# 03_MCU.net
KiCad netlist of a schematic drawn in Altium Designer
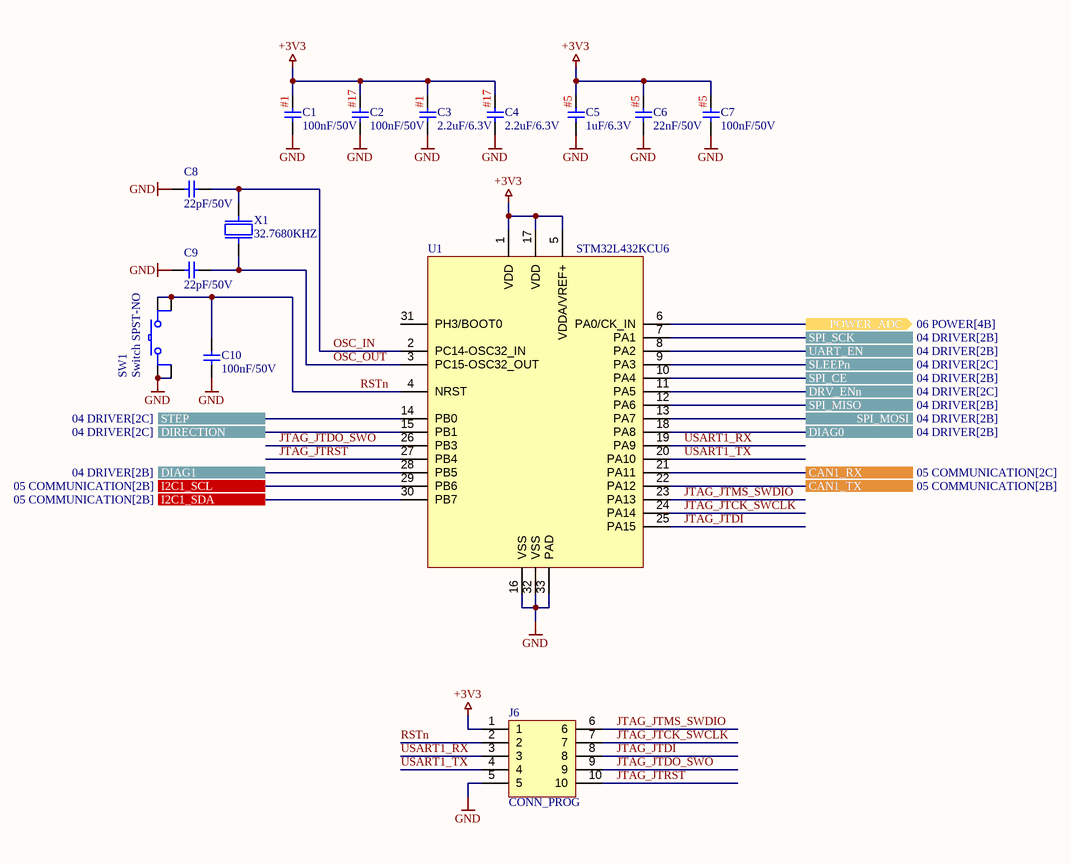
[diagram p0: 03 MCU.SchDoc]

(export (version "E")
  (design (tool "Eeschema 10.0.6"))
  (components
    (comp (ref "C1")
      (value "100nF/50V")
      (footprint "CAPC1005X06M-0402")
      (description "0.1 µF ±10% 50V Ceramic Capacitor X7R 0402 (1005 Metric)")
      (fields (field (name "MPN") "GRM155R71H104KE14D"))
      (libsource (lib "Symbol") (part "GRM155R71H104KE14D"))
    )
    (comp (ref "C2")
      (value "100nF/50V")
      (footprint "CAPC1005X06M-0402")
      (description "0.1 µF ±10% 50V Ceramic Capacitor X7R 0402 (1005 Metric)")
      (fields (field (name "MPN") "GRM155R71H104KE14D"))
      (libsource (lib "Symbol") (part "GRM155R71H104KE14D"))
    )
    (comp (ref "C3")
      (value "2.2uF/6.3V")
      (footprint "CAPC1005X06M-0402")
      (description "2.2 µF ±10% 6.3V Ceramic Capacitor X6S 0402 (1005 Metric)")
      (fields (field (name "MPN") "GRM155C80J225KE95D"))
      (libsource (lib "Symbol") (part "GRM155C80J225KE95D"))
    )
    (comp (ref "C4")
      (value "2.2uF/6.3V")
      (footprint "CAPC1005X06M-0402")
      (description "2.2 µF ±10% 6.3V Ceramic Capacitor X6S 0402 (1005 Metric)")
      (fields (field (name "MPN") "GRM155C80J225KE95D"))
      (libsource (lib "Symbol") (part "GRM155C80J225KE95D"))
    )
    (comp (ref "C5")
      (value "1uF/6.3V")
      (footprint "CAPC1005X06M-0402")
      (description "1 µF ±10% 6.3V Ceramic Capacitor X7R 0402 (1005 Metric)")
      (fields (field (name "MPN") "GRM155R70J105KA12J"))
      (libsource (lib "Symbol") (part "GRM155R70J105KA12J"))
    )
    (comp (ref "C6")
      (value "22nF/50V")
      (footprint "CAPC1005X06M-0402")
      (description "0.022 µF ±10% 50V Ceramic Capacitor X7R 0402 (1005 Metric)")
      (fields (field (name "MPN") "GRM155R71H223KA12D"))
      (libsource (lib "Symbol") (part "GRM155R71H223KA12D"))
    )
    (comp (ref "C7")
      (value "100nF/50V")
      (footprint "CAPC1005X06M-0402")
      (description "0.1 µF ±10% 50V Ceramic Capacitor X7R 0402 (1005 Metric)")
      (fields (field (name "MPN") "GRM155R71H104KE14D"))
      (libsource (lib "Symbol") (part "GRM155R71H104KE14D"))
    )
    (comp (ref "C8")
      (value "22pF/50V")
      (footprint "CAPC1005X06M-0402")
      (description "22 pF ±5% 50V Ceramic Capacitor C0G, NP0 0402 (1005 Metric)")
      (fields (field (name "MPN") "GRM1555C1H220JA01D"))
      (libsource (lib "Symbol") (part "GRM1555C1H220JA01D"))
    )
    (comp (ref "C9")
      (value "22pF/50V")
      (footprint "CAPC1005X06M-0402")
      (description "22 pF ±5% 50V Ceramic Capacitor C0G, NP0 0402 (1005 Metric)")
      (fields (field (name "MPN") "GRM1555C1H220JA01D"))
      (libsource (lib "Symbol") (part "GRM1555C1H220JA01D"))
    )
    (comp (ref "C10")
      (value "100nF/50V")
      (footprint "CAPC1005X06M-0402")
      (description "0.1 µF ±10% 50V Ceramic Capacitor X7R 0402 (1005 Metric)")
      (fields (field (name "MPN") "GRM155R71H104KE14D"))
      (libsource (lib "Symbol") (part "GRM155R71H104KE14D"))
    )
    (comp (ref "J6")
      (value "CONN_PROG")
      (footprint "CONN_PROG")
      (libsource (lib "Symbol") (part "CONN_PROG"))
    )
    (comp (ref "SW1")
      (value "Switch SPST-NO")
      (footprint "PTS815 SJM 250 SMTR LFS")
      (description "Tactile Switch SPST-NO Top Actuated Surface Mount")
      (fields (field (name "MPN") "PTS815 SJM 250 SMTR LFS"))
      (libsource (lib "Symbol") (part "PTS815 SJM 250 SMTR LFS"))
    )
    (comp (ref "U1")
      (value "STM32L432KCU6")
      (footprint "PQFN50P500X500X60_HS-33N")
      (libsource (lib "Symbol") (part "STM32L432KCU6"))
    )
    (comp (ref "X1")
      (value "32.7680KHZ")
      (footprint "2-SMD")
      (description "32.768 kHz ±20ppm Crystal 12.5pF 90 kOhms 2-SMD, No Lead")
      (fields (field (name "MPN") "ECS-.327-12.5-16-TR"))
      (libsource (lib "Symbol") (part "ECS-.327-12.5-16-TR"))
    )
  )
  (nets
    (net (code "1") (name "+3V3") (class "Default")
      (node (ref "C1") (pin "2") (pinfunction "2_2") (pintype "passive"))
      (node (ref "C2") (pin "2") (pinfunction "2_2") (pintype "passive"))
      (node (ref "C3") (pin "2") (pinfunction "2_2") (pintype "passive"))
      (node (ref "C4") (pin "2") (pinfunction "2_2") (pintype "passive"))
      (node (ref "C5") (pin "2") (pinfunction "2_2") (pintype "passive"))
      (node (ref "C6") (pin "2") (pinfunction "2_2") (pintype "passive"))
      (node (ref "C7") (pin "2") (pinfunction "2_2") (pintype "passive"))
      (node (ref "J6") (pin "1") (pinfunction "1_1") (pintype "passive"))
      (node (ref "U1") (pin "1") (pinfunction "VDD_1") (pintype "passive"))
      (node (ref "U1") (pin "17") (pinfunction "VDD_17") (pintype "passive"))
      (node (ref "U1") (pin "5") (pinfunction "VDDA/VREF+_5") (pintype "passive"))
    )
    (net (code "2") (name "/CAN1_RX") (class "Default")
      (node (ref "U1") (pin "21") (pinfunction "PA11_21") (pintype "passive"))
    )
    (net (code "3") (name "/CAN1_TX") (class "Default")
      (node (ref "U1") (pin "22") (pinfunction "PA12_22") (pintype "passive"))
    )
    (net (code "4") (name "/DIAG0") (class "Default")
      (node (ref "U1") (pin "18") (pinfunction "PA8_18") (pintype "passive"))
    )
    (net (code "5") (name "/DIAG1") (class "Default")
      (node (ref "U1") (pin "28") (pinfunction "PB5_28") (pintype "passive"))
    )
    (net (code "6") (name "/DIRECTION") (class "Default")
      (node (ref "U1") (pin "15") (pinfunction "PB1_15") (pintype "passive"))
    )
    (net (code "7") (name "/DRV_ENn") (class "Default")
      (node (ref "U1") (pin "11") (pinfunction "PA5_11") (pintype "passive"))
    )
    (net (code "8") (name "/I2C1_SCL") (class "Default")
      (node (ref "U1") (pin "29") (pinfunction "PB6_29") (pintype "passive"))
    )
    (net (code "9") (name "/I2C1_SDA") (class "Default")
      (node (ref "U1") (pin "30") (pinfunction "PB7_30") (pintype "passive"))
    )
    (net (code "10") (name "/JTAG_JTCK_SWCLK") (class "Default")
      (node (ref "J6") (pin "7") (pinfunction "7_7") (pintype "passive"))
      (node (ref "U1") (pin "24") (pinfunction "PA14_24") (pintype "passive"))
    )
    (net (code "11") (name "/JTAG_JTDI") (class "Default")
      (node (ref "J6") (pin "8") (pinfunction "8_8") (pintype "passive"))
      (node (ref "U1") (pin "25") (pinfunction "PA15_25") (pintype "passive"))
    )
    (net (code "12") (name "/JTAG_JTDO_SWO") (class "Default")
      (node (ref "J6") (pin "9") (pinfunction "9_9") (pintype "passive"))
      (node (ref "U1") (pin "26") (pinfunction "PB3_26") (pintype "passive"))
    )
    (net (code "13") (name "/JTAG_JTMS_SWDIO") (class "Default")
      (node (ref "J6") (pin "6") (pinfunction "6_6") (pintype "passive"))
      (node (ref "U1") (pin "23") (pinfunction "PA13_23") (pintype "passive"))
    )
    (net (code "14") (name "/JTAG_JTRST") (class "Default")
      (node (ref "J6") (pin "10") (pinfunction "10_10") (pintype "passive"))
      (node (ref "U1") (pin "27") (pinfunction "PB4_27") (pintype "passive"))
    )
    (net (code "15") (name "/OSC_IN") (class "Default")
      (node (ref "C8") (pin "2") (pinfunction "2_2") (pintype "passive"))
      (node (ref "U1") (pin "2") (pinfunction "PC14-OSC32_IN_2") (pintype "passive"))
      (node (ref "X1") (pin "2") (pinfunction "2_2") (pintype "passive"))
    )
    (net (code "16") (name "/OSC_OUT") (class "Default")
      (node (ref "C9") (pin "2") (pinfunction "2_2") (pintype "passive"))
      (node (ref "U1") (pin "3") (pinfunction "PC15-OSC32_OUT_3") (pintype "passive"))
      (node (ref "X1") (pin "1") (pinfunction "1_1") (pintype "passive"))
    )
    (net (code "17") (name "/POWER_ADC") (class "Default")
      (node (ref "U1") (pin "6") (pinfunction "PA0/CK_IN_6") (pintype "passive"))
    )
    (net (code "18") (name "/RSTn") (class "Default")
      (node (ref "C10") (pin "2") (pinfunction "2_2") (pintype "passive"))
      (node (ref "J6") (pin "2") (pinfunction "2_2") (pintype "passive"))
      (node (ref "SW1") (pin "3") (pinfunction "3_3") (pintype "passive"))
      (node (ref "SW1") (pin "4") (pinfunction "4_4") (pintype "passive"))
      (node (ref "U1") (pin "4") (pinfunction "NRST_4") (pintype "passive"))
    )
    (net (code "19") (name "/SLEEPn") (class "Default")
      (node (ref "U1") (pin "9") (pinfunction "PA3_9") (pintype "passive"))
    )
    (net (code "20") (name "/SPI_CE") (class "Default")
      (node (ref "U1") (pin "10") (pinfunction "PA4_10") (pintype "passive"))
    )
    (net (code "21") (name "/SPI_MISO") (class "Default")
      (node (ref "U1") (pin "12") (pinfunction "PA6_12") (pintype "passive"))
    )
    (net (code "22") (name "/SPI_MOSI") (class "Default")
      (node (ref "U1") (pin "13") (pinfunction "PA7_13") (pintype "passive"))
    )
    (net (code "23") (name "/SPI_SCK") (class "Default")
      (node (ref "U1") (pin "7") (pinfunction "PA1_7") (pintype "passive"))
    )
    (net (code "24") (name "/STEP") (class "Default")
      (node (ref "U1") (pin "14") (pinfunction "PB0_14") (pintype "passive"))
    )
    (net (code "25") (name "/UART_EN") (class "Default")
      (node (ref "U1") (pin "8") (pinfunction "PA2_8") (pintype "passive"))
    )
    (net (code "26") (name "/USART1_RX") (class "Default")
      (node (ref "J6") (pin "3") (pinfunction "3_3") (pintype "passive"))
      (node (ref "U1") (pin "19") (pinfunction "PA9_19") (pintype "passive"))
    )
    (net (code "27") (name "/USART1_TX") (class "Default")
      (node (ref "J6") (pin "4") (pinfunction "4_4") (pintype "passive"))
      (node (ref "U1") (pin "20") (pinfunction "PA10_20") (pintype "passive"))
    )
    (net (code "28") (name "GND") (class "Default")
      (node (ref "C1") (pin "1") (pinfunction "1_1") (pintype "passive"))
      (node (ref "C10") (pin "1") (pinfunction "1_1") (pintype "passive"))
      (node (ref "C2") (pin "1") (pinfunction "1_1") (pintype "passive"))
      (node (ref "C3") (pin "1") (pinfunction "1_1") (pintype "passive"))
      (node (ref "C4") (pin "1") (pinfunction "1_1") (pintype "passive"))
      (node (ref "C5") (pin "1") (pinfunction "1_1") (pintype "passive"))
      (node (ref "C6") (pin "1") (pinfunction "1_1") (pintype "passive"))
      (node (ref "C7") (pin "1") (pinfunction "1_1") (pintype "passive"))
      (node (ref "C8") (pin "1") (pinfunction "1_1") (pintype "passive"))
      (node (ref "C9") (pin "1") (pinfunction "1_1") (pintype "passive"))
      (node (ref "J6") (pin "5") (pinfunction "5_5") (pintype "passive"))
      (node (ref "SW1") (pin "1") (pinfunction "1_1") (pintype "passive"))
      (node (ref "SW1") (pin "2") (pinfunction "2_2") (pintype "passive"))
      (node (ref "U1") (pin "16") (pinfunction "VSS_16") (pintype "passive"))
      (node (ref "U1") (pin "32") (pinfunction "VSS_32") (pintype "passive"))
      (node (ref "U1") (pin "33") (pinfunction "PAD_33") (pintype "passive"))
    )
    (net (code "29") (name "unconnected-(U1-PH3{slash}BOOT0-Pad31)") (class "Default")
      (node (ref "U1") (pin "31") (pinfunction "PH3/BOOT0_31") (pintype "passive"))
    )
  )
)
